# amebot2_motors.net
KiCad netlist of a schematic drawn in EAGLE
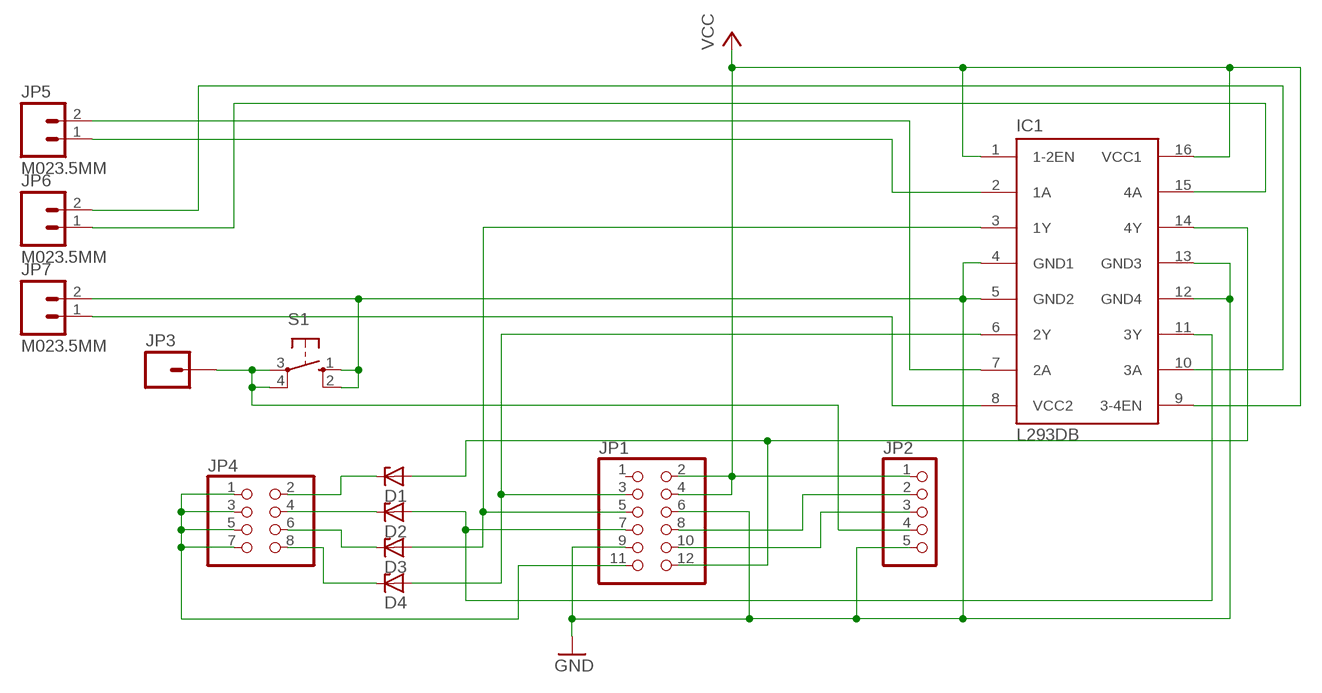
[diagram p0: schematic, sheet 1]

(export (version "E")
  (design (tool "Eeschema 10.0.6"))
  (components
    (comp (ref "D1")
      (value "ZENER-DIODEZD-7.5")
      (footprint "eagle-import:ZDIO-7.5")
      (libsource (lib "eagle-import") (part "ZENER-DIODEZD-7.5"))
    )
    (comp (ref "D2")
      (value "ZENER-DIODEZD-7.5")
      (footprint "eagle-import:ZDIO-7.5")
      (libsource (lib "eagle-import") (part "ZENER-DIODEZD-7.5"))
    )
    (comp (ref "D3")
      (value "ZENER-DIODEZD-7.5")
      (footprint "eagle-import:ZDIO-7.5")
      (libsource (lib "eagle-import") (part "ZENER-DIODEZD-7.5"))
    )
    (comp (ref "D4")
      (value "ZENER-DIODEZD-7.5")
      (footprint "eagle-import:ZDIO-7.5")
      (libsource (lib "eagle-import") (part "ZENER-DIODEZD-7.5"))
    )
    (comp (ref "IC1")
      (value "L293DB")
      (footprint "eagle-import:DIL16VAR")
      (libsource (lib "eagle-import") (part "L293DB"))
    )
    (comp (ref "JP1")
      (value "PINHD-2X6")
      (footprint "eagle-import:2X06")
      (libsource (lib "eagle-import") (part "PINHD-2X6"))
    )
    (comp (ref "JP2")
      (value "PINHD-1X5")
      (footprint "eagle-import:1X05")
      (libsource (lib "eagle-import") (part "PINHD-1X5"))
    )
    (comp (ref "JP3")
      (value "M01PTH_LONGPAD")
      (footprint "eagle-import:1X01_LONGPAD")
      (libsource (lib "eagle-import") (part "M01PTH_LONGPAD"))
    )
    (comp (ref "JP4")
      (value "PINHD-2X4")
      (footprint "eagle-import:2X04")
      (libsource (lib "eagle-import") (part "PINHD-2X4"))
    )
    (comp (ref "JP5")
      (value "M023.5MM")
      (footprint "eagle-import:SCREWTERMINAL-3.5MM-2")
      (libsource (lib "eagle-import") (part "M023.5MM"))
    )
    (comp (ref "JP6")
      (value "M023.5MM")
      (footprint "eagle-import:SCREWTERMINAL-3.5MM-2")
      (libsource (lib "eagle-import") (part "M023.5MM"))
    )
    (comp (ref "JP7")
      (value "M023.5MM")
      (footprint "eagle-import:SCREWTERMINAL-3.5MM-2")
      (libsource (lib "eagle-import") (part "M023.5MM"))
    )
    (comp (ref "S1")
      (value "10-XX")
      (footprint "eagle-import:B3F-10XX")
      (fields (field (name "MPN") "B3F-1000"))
      (libsource (lib "eagle-import") (part "10-XX"))
    )
  )
  (nets
    (net (code "1") (name "GND") (class "Default")
      (node (ref "IC1") (pin "12") (pinfunction "GND4_12") (pintype "power_in"))
      (node (ref "IC1") (pin "13") (pinfunction "GND3_13") (pintype "power_in"))
      (node (ref "IC1") (pin "4") (pinfunction "GND1_4") (pintype "power_in"))
      (node (ref "IC1") (pin "5") (pinfunction "GND2_5") (pintype "power_in"))
      (node (ref "JP1") (pin "6") (pinfunction "6_6") (pintype "passive"))
      (node (ref "JP1") (pin "9") (pinfunction "9_9") (pintype "passive"))
      (node (ref "JP2") (pin "5") (pinfunction "5_5") (pintype "passive"))
      (node (ref "JP7") (pin "2") (pinfunction "2_2") (pintype "passive"))
      (node (ref "S1") (pin "1") (pinfunction "S_1") (pintype "passive"))
      (node (ref "S1") (pin "2") (pinfunction "S1_2") (pintype "passive"))
    )
    (net (code "2") (name "Net-(D1-PadC)") (class "Default")
      (node (ref "D1") (pin "C") (pinfunction "C_C") (pintype "passive"))
      (node (ref "JP4") (pin "2") (pinfunction "2_2") (pintype "passive"))
    )
    (net (code "3") (name "Net-(D2-PadC)") (class "Default")
      (node (ref "D2") (pin "C") (pinfunction "C_C") (pintype "passive"))
      (node (ref "JP4") (pin "4") (pinfunction "4_4") (pintype "passive"))
    )
    (net (code "4") (name "Net-(D3-PadC)") (class "Default")
      (node (ref "D3") (pin "C") (pinfunction "C_C") (pintype "passive"))
      (node (ref "JP4") (pin "6") (pinfunction "6_6") (pintype "passive"))
    )
    (net (code "5") (name "Net-(D4-PadC)") (class "Default")
      (node (ref "D4") (pin "C") (pinfunction "C_C") (pintype "passive"))
      (node (ref "JP4") (pin "8") (pinfunction "8_8") (pintype "passive"))
    )
    (net (code "6") (name "Net-(IC1-1A)") (class "Default")
      (node (ref "IC1") (pin "2") (pinfunction "1A_2") (pintype "input"))
      (node (ref "JP5") (pin "1") (pinfunction "1_1") (pintype "passive"))
    )
    (net (code "7") (name "Net-(IC1-1Y)") (class "Default")
      (node (ref "D3") (pin "A") (pinfunction "A_A") (pintype "passive"))
      (node (ref "IC1") (pin "3") (pinfunction "1Y_3") (pintype "output"))
      (node (ref "JP1") (pin "5") (pinfunction "5_5") (pintype "passive"))
    )
    (net (code "8") (name "Net-(IC1-2A)") (class "Default")
      (node (ref "IC1") (pin "7") (pinfunction "2A_7") (pintype "input"))
      (node (ref "JP5") (pin "2") (pinfunction "2_2") (pintype "passive"))
    )
    (net (code "9") (name "Net-(IC1-2Y)") (class "Default")
      (node (ref "D4") (pin "A") (pinfunction "A_A") (pintype "passive"))
      (node (ref "IC1") (pin "6") (pinfunction "2Y_6") (pintype "output"))
      (node (ref "JP1") (pin "3") (pinfunction "3_3") (pintype "passive"))
    )
    (net (code "10") (name "Net-(IC1-3A)") (class "Default")
      (node (ref "IC1") (pin "10") (pinfunction "3A_10") (pintype "input"))
      (node (ref "JP6") (pin "2") (pinfunction "2_2") (pintype "passive"))
    )
    (net (code "11") (name "Net-(IC1-3Y)") (class "Default")
      (node (ref "D2") (pin "A") (pinfunction "A_A") (pintype "passive"))
      (node (ref "IC1") (pin "11") (pinfunction "3Y_11") (pintype "output"))
      (node (ref "JP1") (pin "7") (pinfunction "7_7") (pintype "passive"))
    )
    (net (code "12") (name "Net-(IC1-4A)") (class "Default")
      (node (ref "IC1") (pin "15") (pinfunction "4A_15") (pintype "input"))
      (node (ref "JP6") (pin "1") (pinfunction "1_1") (pintype "passive"))
    )
    (net (code "13") (name "Net-(IC1-4Y)") (class "Default")
      (node (ref "D1") (pin "A") (pinfunction "A_A") (pintype "passive"))
      (node (ref "IC1") (pin "14") (pinfunction "4Y_14") (pintype "output"))
      (node (ref "JP1") (pin "12") (pinfunction "12_12") (pintype "passive"))
    )
    (net (code "14") (name "Net-(IC1-VCC2)") (class "Default")
      (node (ref "IC1") (pin "8") (pinfunction "VCC2_8") (pintype "power_in"))
      (node (ref "JP7") (pin "1") (pinfunction "1_1") (pintype "passive"))
    )
    (net (code "15") (name "Net-(JP1-Pad8)") (class "Default")
      (node (ref "JP1") (pin "8") (pinfunction "8_8") (pintype "passive"))
      (node (ref "JP2") (pin "2") (pinfunction "2_2") (pintype "passive"))
    )
    (net (code "16") (name "Net-(JP1-Pad10)") (class "Default")
      (node (ref "JP1") (pin "10") (pinfunction "10_10") (pintype "passive"))
      (node (ref "JP2") (pin "3") (pinfunction "3_3") (pintype "passive"))
    )
    (net (code "17") (name "Net-(JP1-Pad11)") (class "Default")
      (node (ref "JP1") (pin "11") (pinfunction "11_11") (pintype "passive"))
      (node (ref "JP4") (pin "1") (pinfunction "1_1") (pintype "passive"))
      (node (ref "JP4") (pin "3") (pinfunction "3_3") (pintype "passive"))
      (node (ref "JP4") (pin "5") (pinfunction "5_5") (pintype "passive"))
      (node (ref "JP4") (pin "7") (pinfunction "7_7") (pintype "passive"))
    )
    (net (code "18") (name "Net-(S1-P)") (class "Default")
      (node (ref "JP2") (pin "4") (pinfunction "4_4") (pintype "passive"))
      (node (ref "JP3") (pin "1") (pinfunction "1_1") (pintype "passive"))
      (node (ref "S1") (pin "3") (pinfunction "P_3") (pintype "passive"))
      (node (ref "S1") (pin "4") (pinfunction "P1_4") (pintype "passive"))
    )
    (net (code "19") (name "VCC") (class "Default")
      (node (ref "IC1") (pin "1") (pinfunction "1-2EN_1") (pintype "input"))
      (node (ref "IC1") (pin "16") (pinfunction "VCC1_16") (pintype "power_in"))
      (node (ref "IC1") (pin "9") (pinfunction "3-4EN_9") (pintype "input"))
      (node (ref "JP1") (pin "2") (pinfunction "2_2") (pintype "passive"))
      (node (ref "JP1") (pin "4") (pinfunction "4_4") (pintype "passive"))
      (node (ref "JP2") (pin "1") (pinfunction "1_1") (pintype "passive"))
    )
    (net (code "20") (name "unconnected-(JP1-Pad1)") (class "Default")
      (node (ref "JP1") (pin "1") (pinfunction "1_1") (pintype "passive"))
    )
  )
)
